# sch.net
KiCad netlist of a schematic drawn in EAGLE
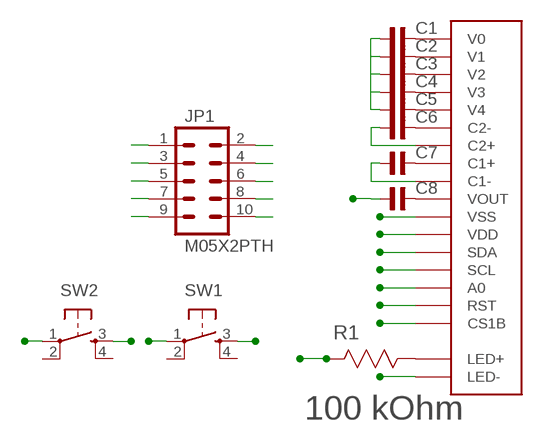
[diagram p0: schematic, sheet 1]

(export (version "E")
  (design (tool "Eeschema 10.0.6"))
  (components
    (comp (ref "C1")
      (value "C-NP-SMD-0603")
      (footprint "eagle-import:C-0603")
      (libsource (lib "eagle-import") (part "C-NP-SMD-0603"))
    )
    (comp (ref "C2")
      (value "C-NP-SMD-0603")
      (footprint "eagle-import:C-0603")
      (libsource (lib "eagle-import") (part "C-NP-SMD-0603"))
    )
    (comp (ref "C3")
      (value "C-NP-SMD-0603")
      (footprint "eagle-import:C-0603")
      (libsource (lib "eagle-import") (part "C-NP-SMD-0603"))
    )
    (comp (ref "C4")
      (value "C-NP-SMD-0603")
      (footprint "eagle-import:C-0603")
      (libsource (lib "eagle-import") (part "C-NP-SMD-0603"))
    )
    (comp (ref "C5")
      (value "C-NP-SMD-0603")
      (footprint "eagle-import:C-0603")
      (libsource (lib "eagle-import") (part "C-NP-SMD-0603"))
    )
    (comp (ref "C6")
      (value "C-NP-SMD-0603")
      (footprint "eagle-import:C-0603")
      (libsource (lib "eagle-import") (part "C-NP-SMD-0603"))
    )
    (comp (ref "C7")
      (value "C-NP-SMD-0603")
      (footprint "eagle-import:C-0603")
      (libsource (lib "eagle-import") (part "C-NP-SMD-0603"))
    )
    (comp (ref "C8")
      (value "C-NP-SMD-0603")
      (footprint "eagle-import:C-0603")
      (libsource (lib "eagle-import") (part "C-NP-SMD-0603"))
    )
    (comp (ref "JP1")
      (value "M05X2PTH")
      (footprint "eagle-import:AVR_ICSP")
      (libsource (lib "eagle-import") (part "M05X2PTH"))
    )
    (comp (ref "R1")
      (value "100 kOhm")
      (footprint "eagle-import:RESC1608X60N")
      (fields (field (name "MPN") "ERA-3AEB104V") (field (name "TOLERANCE") "±0.1%"))
      (libsource (lib "eagle-import") (part "ERA-3AEB104V"))
    )
    (comp (ref "SW1")
      (value "TAC_SWITCHPTH")
      (footprint "eagle-import:TACTILE-PTH")
      (libsource (lib "eagle-import") (part "TAC_SWITCHPTH"))
    )
    (comp (ref "SW2")
      (value "TAC_SWITCHPTH")
      (footprint "eagle-import:TACTILE-PTH")
      (libsource (lib "eagle-import") (part "TAC_SWITCHPTH"))
    )
    (comp (ref "U$1")
      (value "NHD-C12832A1Z-FSW-FBW-3V3")
      (footprint "eagle-import:NHD-C12832A1Z-FSW-FBW-3V3")
      (libsource (lib "eagle-import") (part "NHD-C12832A1Z-FSW-FBW-3V3"))
    )
  )
  (nets
    (net (code "1") (name "/A0") (class "Default")
      (node (ref "JP1") (pin "6") (pinfunction "6_6") (pintype "passive"))
      (node (ref "U$1") (pin "15") (pinfunction "A0_15") (pintype "bidirectional"))
    )
    (net (code "2") (name "/CS1B") (class "Default")
      (node (ref "JP1") (pin "10") (pinfunction "10_10") (pintype "passive"))
      (node (ref "U$1") (pin "17") (pinfunction "CS1B_17") (pintype "bidirectional"))
    )
    (net (code "3") (name "/LED+") (class "Default")
      (node (ref "JP1") (pin "1") (pinfunction "1_1") (pintype "passive"))
      (node (ref "R1") (pin "2") (pinfunction "R2_2") (pintype "passive"))
    )
    (net (code "4") (name "/RST") (class "Default")
      (node (ref "JP1") (pin "8") (pinfunction "8_8") (pintype "passive"))
      (node (ref "U$1") (pin "16") (pinfunction "RST_16") (pintype "bidirectional"))
    )
    (net (code "5") (name "/SCL") (class "Default")
      (node (ref "JP1") (pin "4") (pinfunction "4_4") (pintype "passive"))
      (node (ref "U$1") (pin "14") (pinfunction "SCL_14") (pintype "bidirectional"))
    )
    (net (code "6") (name "/SDA") (class "Default")
      (node (ref "JP1") (pin "2") (pinfunction "2_2") (pintype "passive"))
      (node (ref "U$1") (pin "13") (pinfunction "SDA_13") (pintype "bidirectional"))
    )
    (net (code "7") (name "/SW1") (class "Default")
      (node (ref "JP1") (pin "3") (pinfunction "3_3") (pintype "passive"))
      (node (ref "SW1") (pin "3") (pinfunction "3_3") (pintype "passive"))
    )
    (net (code "8") (name "/SW2") (class "Default")
      (node (ref "JP1") (pin "5") (pinfunction "5_5") (pintype "passive"))
      (node (ref "SW2") (pin "3") (pinfunction "3_3") (pintype "passive"))
    )
    (net (code "9") (name "/VDD") (class "Default")
      (node (ref "JP1") (pin "7") (pinfunction "7_7") (pintype "passive"))
      (node (ref "SW1") (pin "1") (pinfunction "1_1") (pintype "passive"))
      (node (ref "SW2") (pin "1") (pinfunction "1_1") (pintype "passive"))
      (node (ref "U$1") (pin "12") (pinfunction "VDD_12") (pintype "bidirectional"))
    )
    (net (code "10") (name "/VSS") (class "Default")
      (node (ref "C1") (pin "1") (pinfunction "1_1") (pintype "passive"))
      (node (ref "C2") (pin "1") (pinfunction "1_1") (pintype "passive"))
      (node (ref "C3") (pin "1") (pinfunction "1_1") (pintype "passive"))
      (node (ref "C4") (pin "1") (pinfunction "1_1") (pintype "passive"))
      (node (ref "C5") (pin "1") (pinfunction "1_1") (pintype "passive"))
      (node (ref "C8") (pin "1") (pinfunction "1_1") (pintype "passive"))
      (node (ref "JP1") (pin "9") (pinfunction "9_9") (pintype "passive"))
      (node (ref "U$1") (pin "11") (pinfunction "VSS_11") (pintype "bidirectional"))
      (node (ref "U$1") (pin "K") (pinfunction "LED-_K") (pintype "bidirectional"))
    )
    (net (code "11") (name "Net-(R1-R1)") (class "Default")
      (node (ref "R1") (pin "1") (pinfunction "R1_1") (pintype "passive"))
      (node (ref "U$1") (pin "A") (pinfunction "LED+_A") (pintype "bidirectional"))
    )
    (net (code "12") (name "Net-(U$1-C1+)") (class "Default")
      (node (ref "C7") (pin "2") (pinfunction "2_2") (pintype "passive"))
      (node (ref "U$1") (pin "8") (pinfunction "C1+_8") (pintype "bidirectional"))
    )
    (net (code "13") (name "Net-(U$1-C1-)") (class "Default")
      (node (ref "C7") (pin "1") (pinfunction "1_1") (pintype "passive"))
      (node (ref "U$1") (pin "9") (pinfunction "C1-_9") (pintype "bidirectional"))
    )
    (net (code "14") (name "Net-(U$1-C2+)") (class "Default")
      (node (ref "C6") (pin "1") (pinfunction "1_1") (pintype "passive"))
      (node (ref "U$1") (pin "7") (pinfunction "C2+_7") (pintype "bidirectional"))
    )
    (net (code "15") (name "Net-(U$1-C2-)") (class "Default")
      (node (ref "C6") (pin "2") (pinfunction "2_2") (pintype "passive"))
      (node (ref "U$1") (pin "6") (pinfunction "C2-_6") (pintype "bidirectional"))
    )
    (net (code "16") (name "Net-(U$1-V0)") (class "Default")
      (node (ref "C1") (pin "2") (pinfunction "2_2") (pintype "passive"))
      (node (ref "U$1") (pin "1") (pinfunction "V0_1") (pintype "bidirectional"))
    )
    (net (code "17") (name "Net-(U$1-V1)") (class "Default")
      (node (ref "C2") (pin "2") (pinfunction "2_2") (pintype "passive"))
      (node (ref "U$1") (pin "2") (pinfunction "V1_2") (pintype "bidirectional"))
    )
    (net (code "18") (name "Net-(U$1-V2)") (class "Default")
      (node (ref "C3") (pin "2") (pinfunction "2_2") (pintype "passive"))
      (node (ref "U$1") (pin "3") (pinfunction "V2_3") (pintype "bidirectional"))
    )
    (net (code "19") (name "Net-(U$1-V3)") (class "Default")
      (node (ref "C4") (pin "2") (pinfunction "2_2") (pintype "passive"))
      (node (ref "U$1") (pin "4") (pinfunction "V3_4") (pintype "bidirectional"))
    )
    (net (code "20") (name "Net-(U$1-V4)") (class "Default")
      (node (ref "C5") (pin "2") (pinfunction "2_2") (pintype "passive"))
      (node (ref "U$1") (pin "5") (pinfunction "V4_5") (pintype "bidirectional"))
    )
    (net (code "21") (name "Net-(U$1-VOUT)") (class "Default")
      (node (ref "C8") (pin "2") (pinfunction "2_2") (pintype "passive"))
      (node (ref "U$1") (pin "10") (pinfunction "VOUT_10") (pintype "bidirectional"))
    )
    (net (code "22") (name "unconnected-(SW1-Pad2)") (class "Default")
      (node (ref "SW1") (pin "2") (pinfunction "2_2") (pintype "passive"))
    )
    (net (code "23") (name "unconnected-(SW1-Pad4)") (class "Default")
      (node (ref "SW1") (pin "4") (pinfunction "4_4") (pintype "passive"))
    )
    (net (code "24") (name "unconnected-(SW2-Pad2)") (class "Default")
      (node (ref "SW2") (pin "2") (pinfunction "2_2") (pintype "passive"))
    )
    (net (code "25") (name "unconnected-(SW2-Pad4)") (class "Default")
      (node (ref "SW2") (pin "4") (pinfunction "4_4") (pintype "passive"))
    )
  )
)
